# IFREMER_ADD_ON.net
KiCad netlist of a schematic drawn in Altium Designer
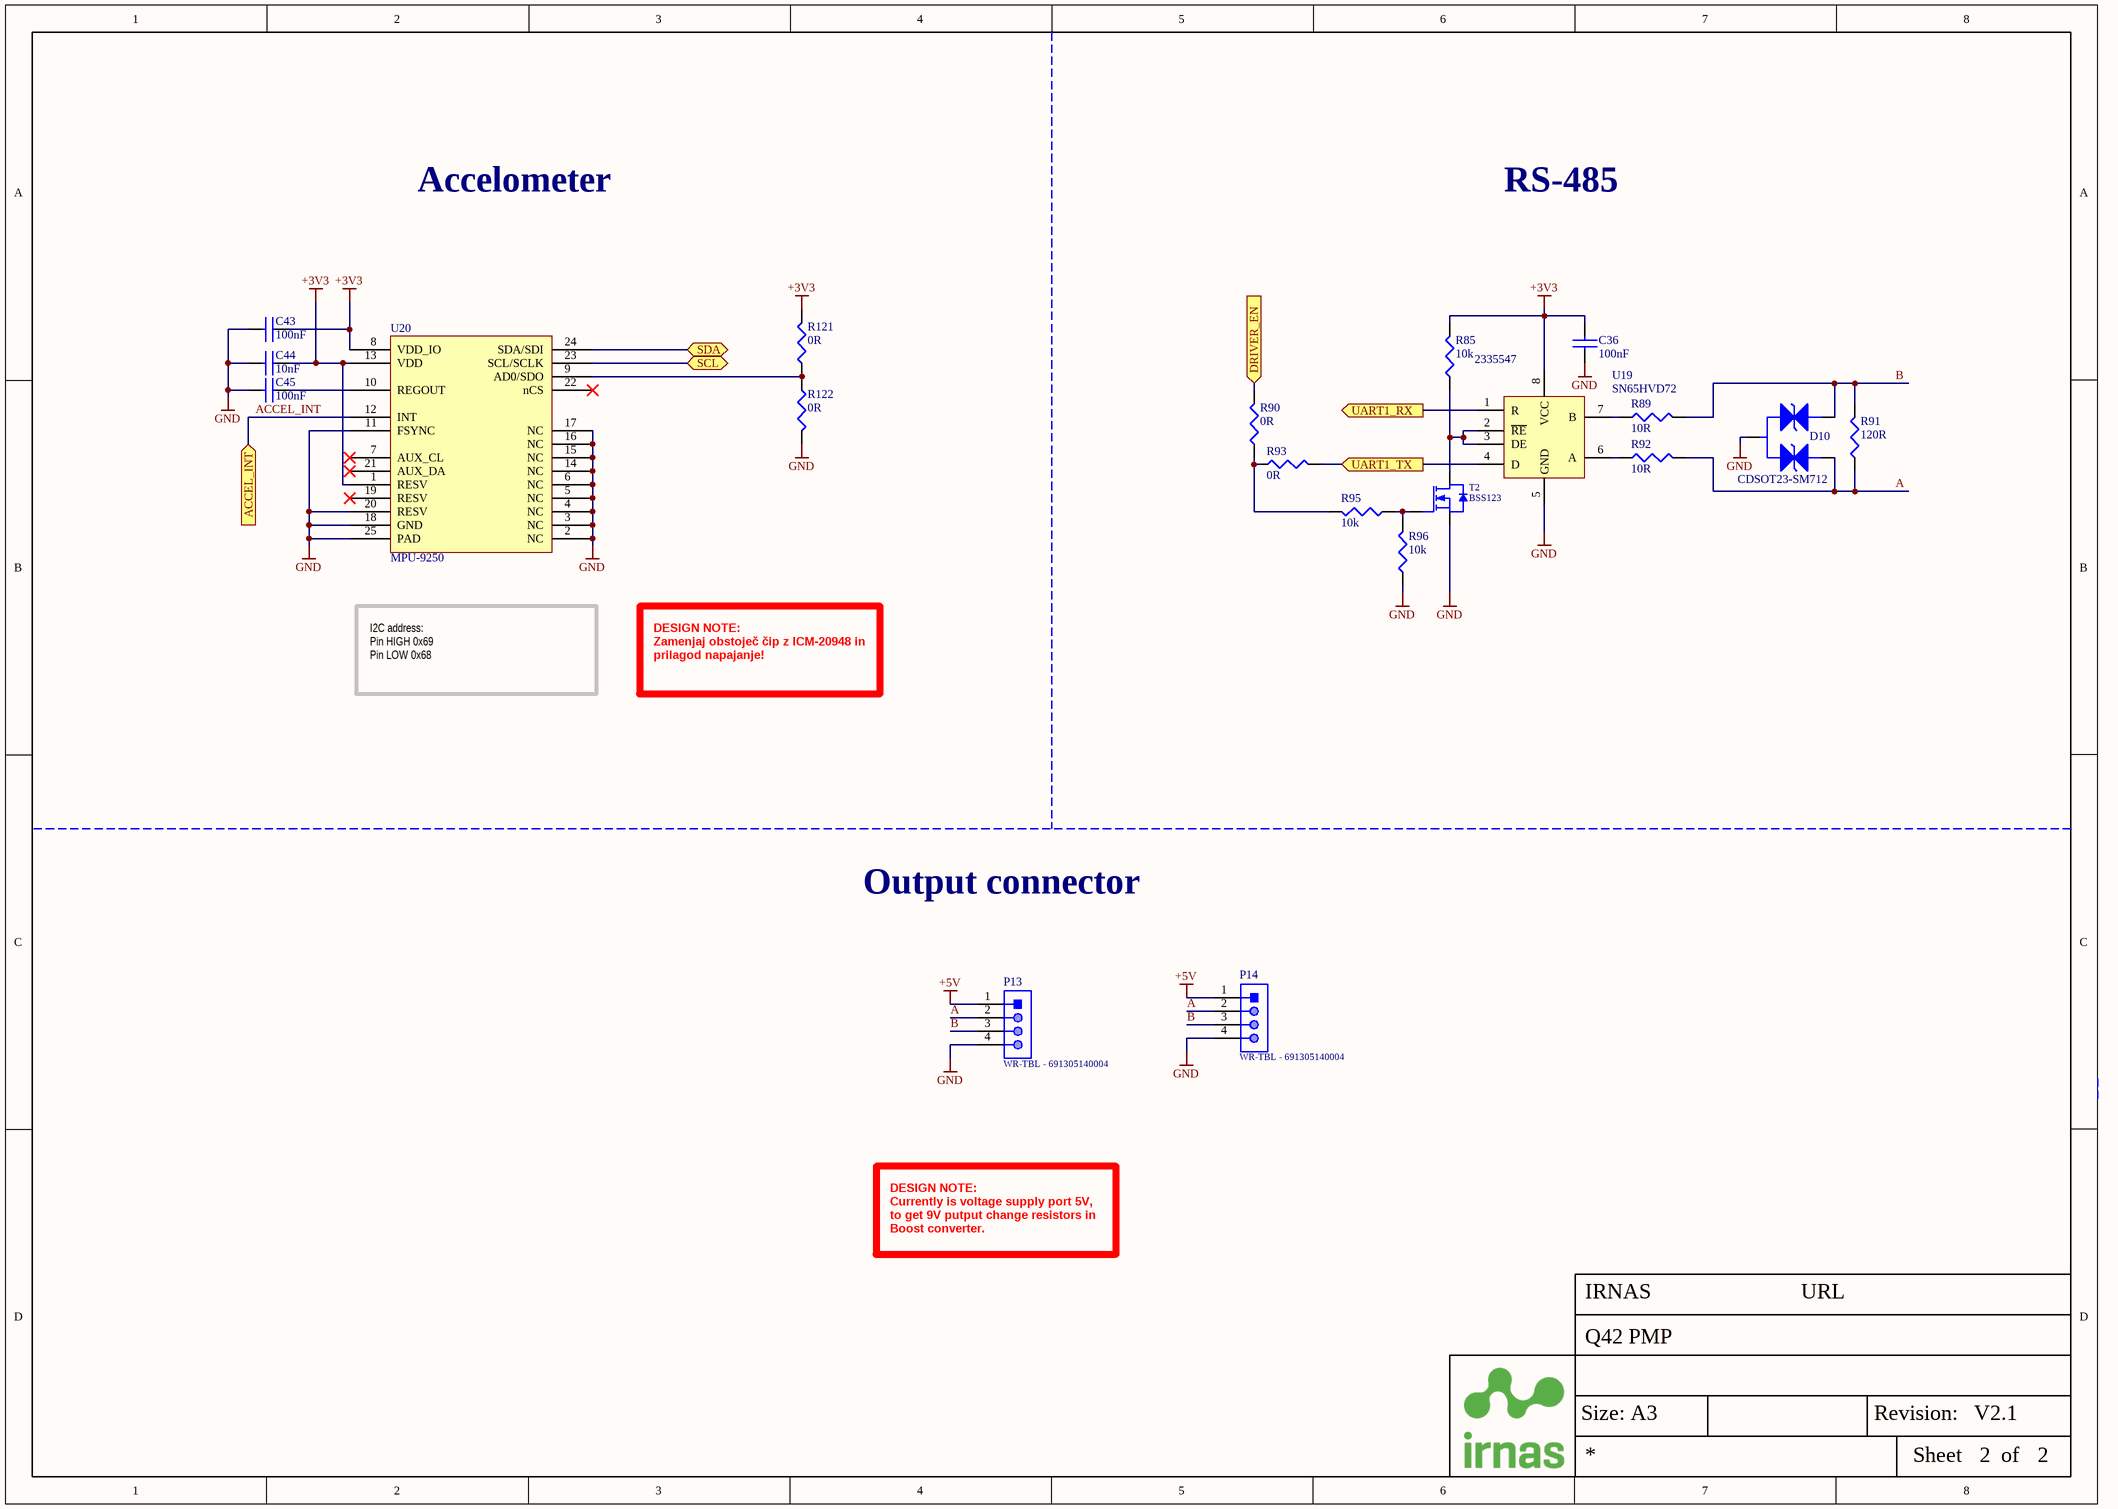
[diagram p0: IFREMER ADD ON.SchDoc]

(export (version "E")
  (design (tool "Eeschema 10.0.6"))
  (components
    (comp (ref "C36")
      (value "100nF")
      (footprint "CAP0603")
      (description "MURATA - GRM188R71C104KA01J - CAP, MLCC, X7R, 0.1UF, 16V, 0603")
      (fields
        (field (name "MANUFACTURER") "MURATA")
        (field (name "MANUFACTURER PART NUMBER") "GRM188R71C104KA01J")
      )
      (libsource (lib "Passive") (part "C - 100nF"))
    )
    (comp (ref "C43")
      (value "100nF")
      (footprint "CAP0603")
      (description "MURATA - GRM188R71C104KA01J - CAP, MLCC, X7R, 0.1UF, 16V, 0603")
      (fields
        (field (name "MANUFACTURER") "MURATA")
        (field (name "MANUFACTURER PART NUMBER") "GRM188R71C104KA01J")
      )
      (libsource (lib "Passive") (part "C - 100nF"))
    )
    (comp (ref "C44")
      (value "10nF")
      (footprint "CAP0603")
      (description "KEMET - C0603X103K5RECAUTO - CAP, MLCC, AEC-Q200, X7R, 0.01UF, 50V")
      (fields
        (field (name "MANUFACTURER") "TDK EPCOS")
        (field (name "MANUFACTURER PART NUMBER") "C0603X103K5RECAUTO")
      )
      (libsource (lib "Passive") (part "C - 10nF"))
    )
    (comp (ref "C45")
      (value "100nF")
      (footprint "CAP0603")
      (description "MURATA - GRM188R71C104KA01J - CAP, MLCC, X7R, 0.1UF, 16V, 0603")
      (fields
        (field (name "MANUFACTURER") "MURATA")
        (field (name "MANUFACTURER PART NUMBER") "GRM188R71C104KA01J")
      )
      (libsource (lib "Passive") (part "C - 100nF"))
    )
    (comp (ref "D10")
      (value "CDSOT23-SM712")
      (footprint "SOT23-3AL")
      (description "TVS Diode, CDSOT23 Series, Bidirectional, 12 V, 26 V, SOT-23, 3 Pins")
      (fields
        (field (name "MANUFACTURER") "DIODES INC.")
        (field (name "MANUFACTURER PART NUMBER") "1N4148W-7-F.")
      )
      (libsource (lib "Active") (part "D_TVS - CDSOT23-SM712"))
    )
    (comp (ref "P13")
      (value "WR-TBL - 691305140004")
      (footprint "691305140004")
      (description "Serie 3051 - 3.50mm Horizontal PCB Header with Plastic Latch WR-TBL, 4 pin")
      (fields (field (name "PART NUMBER") "691305140004") (field (name "PUBLISHER") "Wurth Elektronik"))
      (libsource (lib "Connectors") (part "WR-TBL - 691305140004"))
    )
    (comp (ref "P14")
      (value "WR-TBL - 691305140004")
      (footprint "691305140004")
      (description "Serie 3051 - 3.50mm Horizontal PCB Header with Plastic Latch WR-TBL, 4 pin")
      (fields (field (name "PART NUMBER") "691305140004") (field (name "PUBLISHER") "Wurth Elektronik"))
      (libsource (lib "Connectors") (part "WR-TBL - 691305140004"))
    )
    (comp (ref "R85")
      (value "10k")
      (footprint "RES0603")
      (description "MULTICOMP - MCMR06X103 JTL - RES, CERAMIC, 10K, 5%, 0.1W, 0603")
      (fields
        (field (name "MANUFACTURER") "MULTICOMP")
        (field (name "MANUFACTURER PART NUMBER") "MCMR06X103 JTL")
      )
      (libsource (lib "Passive") (part "R - 10k"))
    )
    (comp (ref "R89")
      (value "10R")
      (footprint "RES0603")
      (description "VISHAY - RCA060310R0FKEA - RES, AUTO, THICK FILM, 10R, 1%, 0603")
      (fields
        (field (name "MANUFACTURER") "VISHAY")
        (field (name "MANUFACTURER PART NUMBER") "RCA060310R0FKEA")
      )
      (libsource (lib "Passive") (part "R - 10R"))
    )
    (comp (ref "R90")
      (value "0R")
      (footprint "RES0603")
      (description "BOURNS - CR0603-J/-000ELF - RES, THICK FILM, 0R, 5%, 0.1W, 0603")
      (fields
        (field (name "MANUFACTURER") "BOURNS")
        (field (name "MANUFACTURER PART NUMBER") "CR0603-J/-000ELF")
      )
      (libsource (lib "Passive") (part "R - 0R"))
    )
    (comp (ref "R91")
      (value "120R")
      (footprint "RES0603")
      (description "RES SMD 120 OHM 1% 1/4W 0603")
      (fields
        (field (name "MANUFACTURER") "Vishay")
        (field (name "MANUFACTURER PART NUMBER") "CRCW0603120RFKEAHP")
      )
      (libsource (lib "Passive") (part "R - 120R"))
    )
    (comp (ref "R92")
      (value "10R")
      (footprint "RES0603")
      (description "VISHAY - RCA060310R0FKEA - RES, AUTO, THICK FILM, 10R, 1%, 0603")
      (fields
        (field (name "MANUFACTURER") "VISHAY")
        (field (name "MANUFACTURER PART NUMBER") "RCA060310R0FKEA")
      )
      (libsource (lib "Passive") (part "R - 10R"))
    )
    (comp (ref "R93")
      (value "0R")
      (footprint "RES0603")
      (description "BOURNS - CR0603-J/-000ELF - RES, THICK FILM, 0R, 5%, 0.1W, 0603")
      (fields
        (field (name "MANUFACTURER") "BOURNS")
        (field (name "MANUFACTURER PART NUMBER") "CR0603-J/-000ELF")
      )
      (libsource (lib "Passive") (part "R - 0R"))
    )
    (comp (ref "R95")
      (value "10k")
      (footprint "RES0603")
      (description "MULTICOMP - MCMR06X103 JTL - RES, CERAMIC, 10K, 5%, 0.1W, 0603")
      (fields
        (field (name "MANUFACTURER") "MULTICOMP")
        (field (name "MANUFACTURER PART NUMBER") "MCMR06X103 JTL")
      )
      (libsource (lib "Passive") (part "R - 10k"))
    )
    (comp (ref "R96")
      (value "10k")
      (footprint "RES0603")
      (description "MULTICOMP - MCMR06X103 JTL - RES, CERAMIC, 10K, 5%, 0.1W, 0603")
      (fields
        (field (name "MANUFACTURER") "MULTICOMP")
        (field (name "MANUFACTURER PART NUMBER") "MCMR06X103 JTL")
      )
      (libsource (lib "Passive") (part "R - 10k"))
    )
    (comp (ref "R121")
      (value "0R")
      (footprint "RES0603")
      (description "BOURNS - CR0603-J/-000ELF - RES, THICK FILM, 0R, 5%, 0.1W, 0603")
      (fields
        (field (name "MANUFACTURER") "BOURNS")
        (field (name "MANUFACTURER PART NUMBER") "CR0603-J/-000ELF")
      )
      (libsource (lib "Passive") (part "R - 0R"))
    )
    (comp (ref "R122")
      (value "0R")
      (footprint "RES0603")
      (description "BOURNS - CR0603-J/-000ELF - RES, THICK FILM, 0R, 5%, 0.1W, 0603")
      (fields
        (field (name "MANUFACTURER") "BOURNS")
        (field (name "MANUFACTURER PART NUMBER") "CR0603-J/-000ELF")
      )
      (libsource (lib "Passive") (part "R - 0R"))
    )
    (comp (ref "T2")
      (value "BSS123")
      (footprint "Active:SOT23-3AL")
      (description "N-Channel Vds = 100V, Id = 170 mA")
      (libsource (lib "Active") (part "T_M - BSS123"))
    )
    (comp (ref "U19")
      (value "SN65HVD72")
      (footprint "SOIC-8 REFLOW")
      (fields (field (name "SUPPLIER PART NUMBER 1") "2335547"))
      (libsource (lib "Active") (part "INT - SN65HVD72"))
    )
    (comp (ref "U20")
      (value "MPU-9250")
      (footprint "QFN40P300X300X105_HS-25N")
      (description "IMU ACCEL/GYRO/MAG I2C/SPI 24QFN")
      (fields (field (name "MANUFACTURER") "TDK InvenSense"))
      (libsource (lib "Active") (part "SEN - MPU-9250"))
    )
  )
  (nets
    (net (code "1") (name "+3V3") (class "Default")
      (node (ref "C36") (pin "2") (pinfunction "2_2") (pintype "passive"))
      (node (ref "C43") (pin "1") (pinfunction "1_1") (pintype "passive"))
      (node (ref "C44") (pin "1") (pinfunction "1_1") (pintype "passive"))
      (node (ref "R121") (pin "2") (pinfunction "2_2") (pintype "passive"))
      (node (ref "R85") (pin "2") (pinfunction "2_2") (pintype "passive"))
      (node (ref "U19") (pin "8") (pinfunction "VCC_8") (pintype "passive"))
      (node (ref "U20") (pin "1") (pinfunction "RESV_1") (pintype "passive"))
      (node (ref "U20") (pin "13") (pinfunction "VDD_13") (pintype "passive"))
      (node (ref "U20") (pin "8") (pinfunction "VDD_IO_8") (pintype "passive"))
    )
    (net (code "2") (name "+5V") (class "Default")
      (node (ref "P13") (pin "1") (pinfunction "1_1") (pintype "passive"))
      (node (ref "P14") (pin "1") (pinfunction "1_1") (pintype "passive"))
    )
    (net (code "3") (name "/A") (class "Default")
      (node (ref "D10") (pin "2") (pinfunction "cathode_2") (pintype "passive"))
      (node (ref "P13") (pin "2") (pinfunction "2_2") (pintype "passive"))
      (node (ref "P14") (pin "2") (pinfunction "2_2") (pintype "passive"))
      (node (ref "R91") (pin "1") (pinfunction "1_1") (pintype "passive"))
      (node (ref "R92") (pin "2") (pinfunction "2_2") (pintype "passive"))
    )
    (net (code "4") (name "/ACCEL_INT") (class "Default")
      (node (ref "U20") (pin "12") (pinfunction "INT_12") (pintype "passive"))
    )
    (net (code "5") (name "/B") (class "Default")
      (node (ref "D10") (pin "1") (pinfunction "cathode_1") (pintype "passive"))
      (node (ref "P13") (pin "3") (pinfunction "3_3") (pintype "passive"))
      (node (ref "P14") (pin "3") (pinfunction "3_3") (pintype "passive"))
      (node (ref "R89") (pin "2") (pinfunction "2_2") (pintype "passive"))
      (node (ref "R91") (pin "2") (pinfunction "2_2") (pintype "passive"))
    )
    (net (code "6") (name "/DRIVER_EN") (class "Default")
      (node (ref "R90") (pin "2") (pinfunction "2_2") (pintype "passive"))
    )
    (net (code "7") (name "/SCL") (class "Default")
      (node (ref "U20") (pin "23") (pinfunction "SCL/SCLK_23") (pintype "passive"))
    )
    (net (code "8") (name "/SDA") (class "Default")
      (node (ref "U20") (pin "24") (pinfunction "SDA/SDI_24") (pintype "passive"))
    )
    (net (code "9") (name "/UART1_RX") (class "Default")
      (node (ref "U19") (pin "1") (pinfunction "R_1") (pintype "passive"))
    )
    (net (code "10") (name "/UART1_TX") (class "Default")
      (node (ref "R93") (pin "2") (pinfunction "2_2") (pintype "passive"))
      (node (ref "U19") (pin "4") (pinfunction "D_4") (pintype "passive"))
    )
    (net (code "11") (name "GND") (class "Default")
      (node (ref "C36") (pin "1") (pinfunction "1_1") (pintype "passive"))
      (node (ref "C43") (pin "2") (pinfunction "2_2") (pintype "passive"))
      (node (ref "C44") (pin "2") (pinfunction "2_2") (pintype "passive"))
      (node (ref "C45") (pin "2") (pinfunction "2_2") (pintype "passive"))
      (node (ref "D10") (pin "3") (pinfunction "ANODE_3") (pintype "passive"))
      (node (ref "P13") (pin "4") (pinfunction "4_4") (pintype "passive"))
      (node (ref "P14") (pin "4") (pinfunction "4_4") (pintype "passive"))
      (node (ref "R122") (pin "2") (pinfunction "2_2") (pintype "passive"))
      (node (ref "R96") (pin "1") (pinfunction "1_1") (pintype "passive"))
      (node (ref "T2") (pin "2") (pinfunction "S_2") (pintype "passive"))
      (node (ref "U19") (pin "5") (pinfunction "GND_5") (pintype "passive"))
      (node (ref "U20") (pin "11") (pinfunction "FSYNC_11") (pintype "passive"))
      (node (ref "U20") (pin "14") (pinfunction "NC_14") (pintype "passive"))
      (node (ref "U20") (pin "15") (pinfunction "NC_15") (pintype "passive"))
      (node (ref "U20") (pin "16") (pinfunction "NC_16") (pintype "passive"))
      (node (ref "U20") (pin "17") (pinfunction "NC_17") (pintype "passive"))
      (node (ref "U20") (pin "18") (pinfunction "GND_18") (pintype "passive"))
      (node (ref "U20") (pin "2") (pinfunction "NC_2") (pintype "passive"))
      (node (ref "U20") (pin "20") (pinfunction "RESV_20") (pintype "passive"))
      (node (ref "U20") (pin "25") (pinfunction "PAD_25") (pintype "passive"))
      (node (ref "U20") (pin "3") (pinfunction "NC_3") (pintype "passive"))
      (node (ref "U20") (pin "4") (pinfunction "NC_4") (pintype "passive"))
      (node (ref "U20") (pin "5") (pinfunction "NC_5") (pintype "passive"))
      (node (ref "U20") (pin "6") (pinfunction "NC_6") (pintype "passive"))
    )
    (net (code "12") (name "Net-(R90-Pad1)") (class "Default")
      (node (ref "R90") (pin "1") (pinfunction "1_1") (pintype "passive"))
      (node (ref "R93") (pin "1") (pinfunction "1_1") (pintype "passive"))
      (node (ref "R95") (pin "2") (pinfunction "2_2") (pintype "passive"))
    )
    (net (code "13") (name "Net-(T2-D)") (class "Default")
      (node (ref "R85") (pin "1") (pinfunction "1_1") (pintype "passive"))
      (node (ref "T2") (pin "3") (pinfunction "D_3") (pintype "passive"))
      (node (ref "U19") (pin "2") (pinfunction "~{RE}_2") (pintype "passive"))
      (node (ref "U19") (pin "3") (pinfunction "DE_3") (pintype "passive"))
    )
    (net (code "14") (name "Net-(T2-G)") (class "Default")
      (node (ref "R95") (pin "1") (pinfunction "1_1") (pintype "passive"))
      (node (ref "R96") (pin "2") (pinfunction "2_2") (pintype "passive"))
      (node (ref "T2") (pin "1") (pinfunction "G_1") (pintype "passive"))
    )
    (net (code "15") (name "Net-(U19-A)") (class "Default")
      (node (ref "R92") (pin "1") (pinfunction "1_1") (pintype "passive"))
      (node (ref "U19") (pin "6") (pinfunction "A_6") (pintype "passive"))
    )
    (net (code "16") (name "Net-(U19-B)") (class "Default")
      (node (ref "R89") (pin "1") (pinfunction "1_1") (pintype "passive"))
      (node (ref "U19") (pin "7") (pinfunction "B_7") (pintype "passive"))
    )
    (net (code "17") (name "Net-(U20-AD0{slash}SDO)") (class "Default")
      (node (ref "R121") (pin "1") (pinfunction "1_1") (pintype "passive"))
      (node (ref "R122") (pin "1") (pinfunction "1_1") (pintype "passive"))
      (node (ref "U20") (pin "9") (pinfunction "AD0/SDO_9") (pintype "passive"))
    )
    (net (code "18") (name "Net-(U20-REGOUT)") (class "Default")
      (node (ref "C45") (pin "1") (pinfunction "1_1") (pintype "passive"))
      (node (ref "U20") (pin "10") (pinfunction "REGOUT_10") (pintype "passive"))
    )
    (net (code "19") (name "unconnected-(U20-AUX_CL-Pad7)") (class "Default")
      (node (ref "U20") (pin "7") (pinfunction "AUX_CL_7") (pintype "passive+no_connect"))
    )
    (net (code "20") (name "unconnected-(U20-AUX_DA-Pad21)") (class "Default")
      (node (ref "U20") (pin "21") (pinfunction "AUX_DA_21") (pintype "passive+no_connect"))
    )
    (net (code "21") (name "unconnected-(U20-RESV-Pad19)") (class "Default")
      (node (ref "U20") (pin "19") (pinfunction "RESV_19") (pintype "passive+no_connect"))
    )
    (net (code "22") (name "unconnected-(U20-nCS-Pad22)") (class "Default")
      (node (ref "U20") (pin "22") (pinfunction "nCS_22") (pintype "passive+no_connect"))
    )
  )
)
